# grizzly_bear.net
KiCad netlist of a schematic drawn in EAGLE
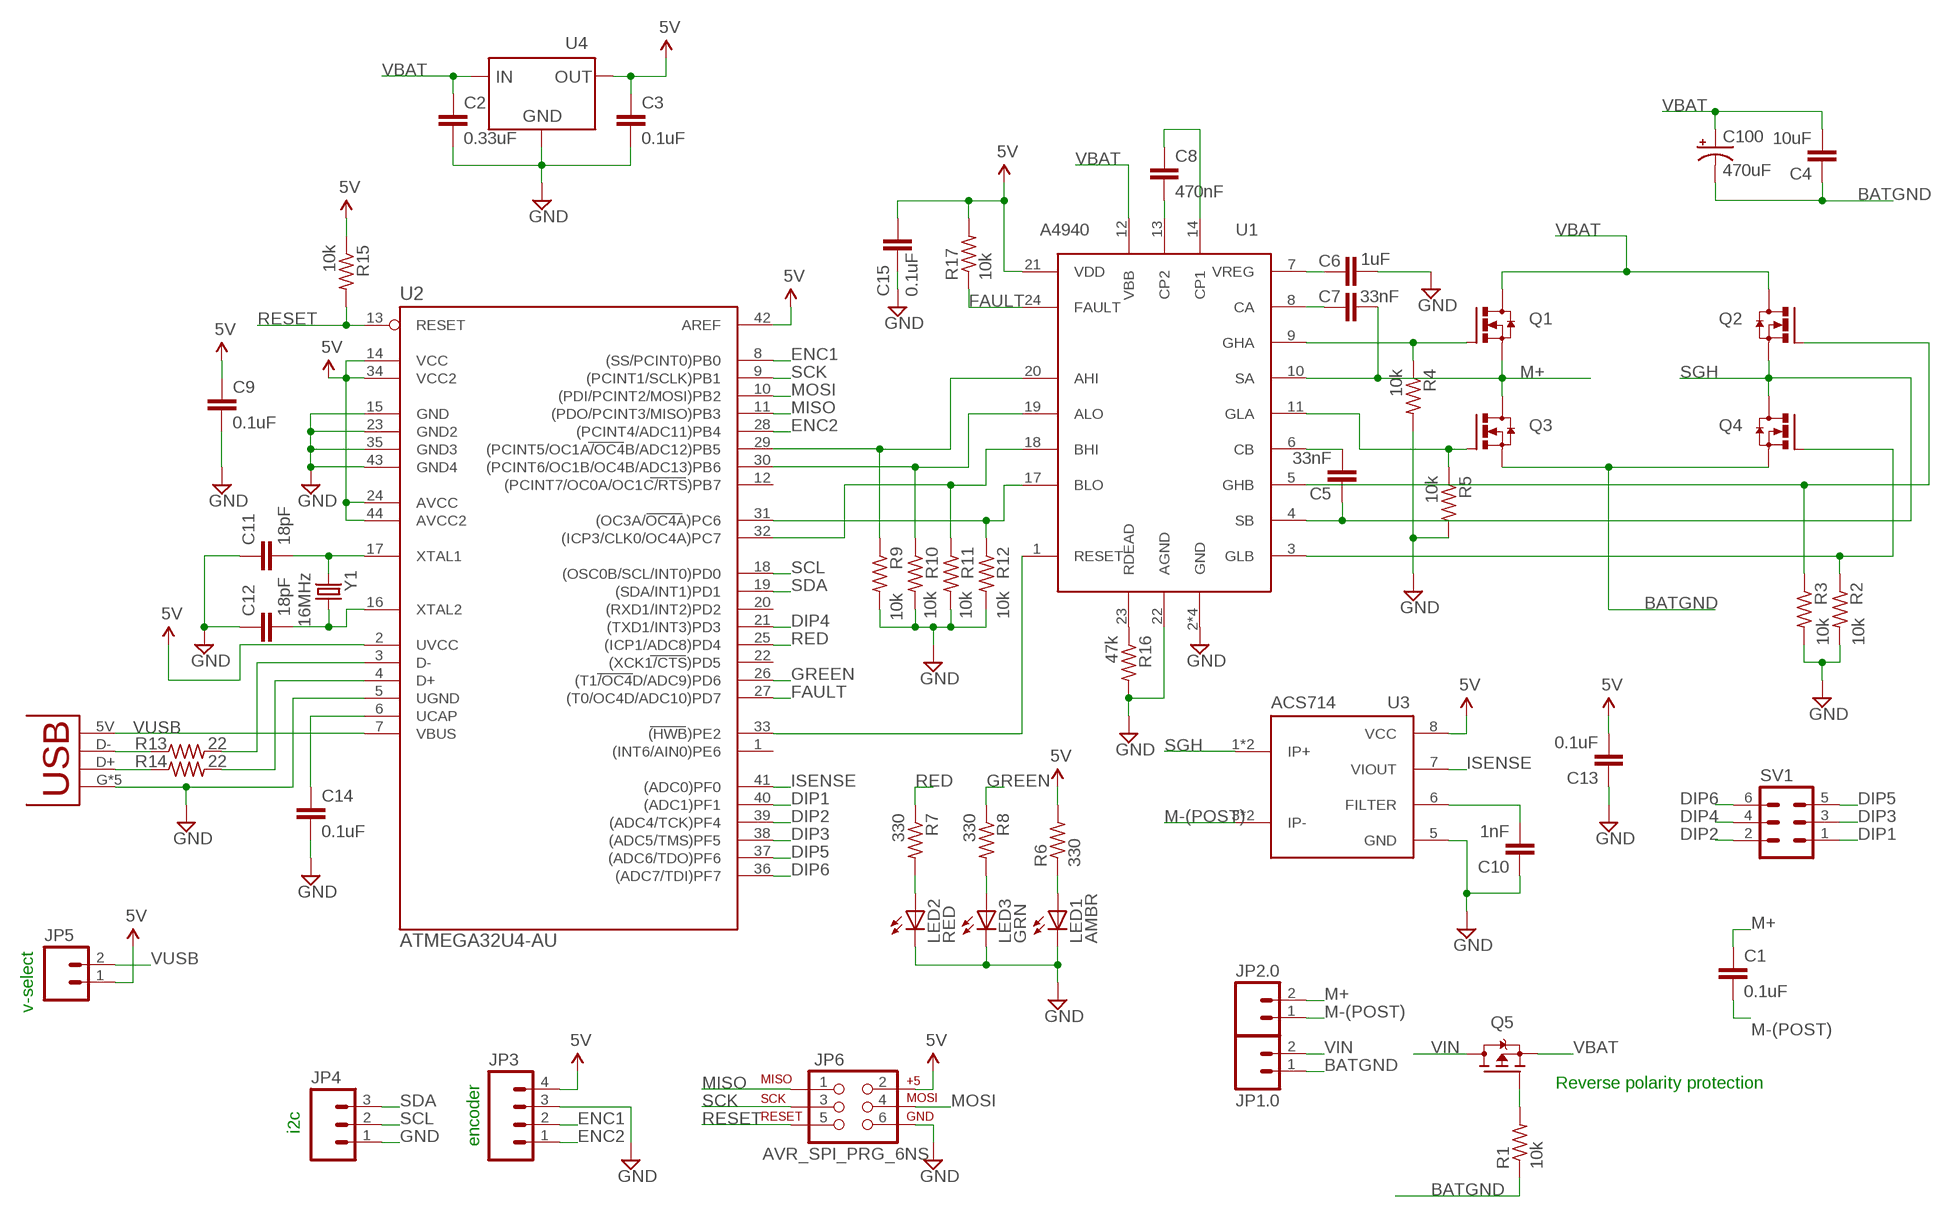
[diagram p0: schematic, sheet 1]

(export (version "E")
  (design (tool "Eeschema 10.0.6"))
  (components
    (comp (ref "C1")
      (value "0.1uF")
      (footprint "eagle-import:0603-CAP")
      (libsource (lib "eagle-import") (part "CAP0603-CAP"))
    )
    (comp (ref "C2")
      (value "0.33uF")
      (footprint "eagle-import:0603-CAP")
      (libsource (lib "eagle-import") (part "CAP0603-CAP"))
    )
    (comp (ref "C3")
      (value "0.1uF")
      (footprint "eagle-import:0603-CAP")
      (libsource (lib "eagle-import") (part "CAP0603-CAP"))
    )
    (comp (ref "C4")
      (value "10uF")
      (footprint "eagle-import:0603-CAP")
      (libsource (lib "eagle-import") (part "CAP0603-CAP"))
    )
    (comp (ref "C5")
      (value "33nF")
      (footprint "eagle-import:0603-CAP")
      (libsource (lib "eagle-import") (part "CAP0603-CAP"))
    )
    (comp (ref "C6")
      (value "1uF")
      (footprint "eagle-import:0603-CAP")
      (libsource (lib "eagle-import") (part "CAP0603-CAP"))
    )
    (comp (ref "C7")
      (value "33nF")
      (footprint "eagle-import:0603-CAP")
      (libsource (lib "eagle-import") (part "CAP0603-CAP"))
    )
    (comp (ref "C8")
      (value "470nF")
      (footprint "eagle-import:0603-CAP")
      (libsource (lib "eagle-import") (part "CAP0603-CAP"))
    )
    (comp (ref "C9")
      (value "0.1uF")
      (footprint "eagle-import:0603-CAP")
      (libsource (lib "eagle-import") (part "CAP0603-CAP"))
    )
    (comp (ref "C10")
      (value "1nF")
      (footprint "eagle-import:0603-CAP")
      (libsource (lib "eagle-import") (part "CAP0603-CAP"))
    )
    (comp (ref "C11")
      (value "18pF")
      (footprint "eagle-import:0603-CAP")
      (libsource (lib "eagle-import") (part "CAP0603-CAP"))
    )
    (comp (ref "C12")
      (value "18pF")
      (footprint "eagle-import:0603-CAP")
      (libsource (lib "eagle-import") (part "CAP0603-CAP"))
    )
    (comp (ref "C13")
      (value "0.1uF")
      (footprint "eagle-import:0603-CAP")
      (libsource (lib "eagle-import") (part "CAP0603-CAP"))
    )
    (comp (ref "C14")
      (value "0.1uF")
      (footprint "eagle-import:0603-CAP")
      (libsource (lib "eagle-import") (part "CAP0603-CAP"))
    )
    (comp (ref "C15")
      (value "0.1uF")
      (footprint "eagle-import:0603-CAP")
      (libsource (lib "eagle-import") (part "CAP0603-CAP"))
    )
    (comp (ref "C100")
      (value "470uF")
      (footprint "eagle-import:PANASONIC_G")
      (libsource (lib "eagle-import") (part "CAP_POLG"))
    )
    (comp (ref "JP1.0")
      (value "M02PTH4")
      (footprint "eagle-import:1X02_XTRA_BIG")
      (libsource (lib "eagle-import") (part "M02PTH4"))
    )
    (comp (ref "JP2.0")
      (value "M02PTH4")
      (footprint "eagle-import:1X02_XTRA_BIG")
      (libsource (lib "eagle-import") (part "M02PTH4"))
    )
    (comp (ref "JP3")
      (value "M04POLAR")
      (footprint "eagle-import:MOLEX-1X4")
      (libsource (lib "eagle-import") (part "M04POLAR"))
    )
    (comp (ref "JP4")
      (value "M03POLAR")
      (footprint "eagle-import:MOLEX-1X3")
      (libsource (lib "eagle-import") (part "M03POLAR"))
    )
    (comp (ref "JP5")
      (value "M02LOCK")
      (footprint "eagle-import:1X02_LOCK")
      (libsource (lib "eagle-import") (part "M02LOCK"))
    )
    (comp (ref "JP6")
      (value "AVR_SPI_PRG_6NS")
      (footprint "eagle-import:2X3-NS")
      (libsource (lib "eagle-import") (part "AVR_SPI_PRG_6NS"))
    )
    (comp (ref "LED1")
      (value "AMBR")
      (footprint "eagle-import:LED-1206")
      (libsource (lib "eagle-import") (part "LED1206"))
    )
    (comp (ref "LED2")
      (value "RED")
      (footprint "eagle-import:LED-1206")
      (libsource (lib "eagle-import") (part "LED1206"))
    )
    (comp (ref "LED3")
      (value "GRN")
      (footprint "eagle-import:LED-1206")
      (libsource (lib "eagle-import") (part "LED1206"))
    )
    (comp (ref "Q1")
      (value "N-CHANNEL-MOSFET")
      (footprint "eagle-import:SOT669")
      (libsource (lib "eagle-import") (part "N-CHANNEL-MOSFET"))
    )
    (comp (ref "Q2")
      (value "N-CHANNEL-MOSFET")
      (footprint "eagle-import:SOT669")
      (libsource (lib "eagle-import") (part "N-CHANNEL-MOSFET"))
    )
    (comp (ref "Q3")
      (value "N-CHANNEL-MOSFET")
      (footprint "eagle-import:SOT669")
      (libsource (lib "eagle-import") (part "N-CHANNEL-MOSFET"))
    )
    (comp (ref "Q4")
      (value "N-CHANNEL-MOSFET")
      (footprint "eagle-import:SOT669")
      (libsource (lib "eagle-import") (part "N-CHANNEL-MOSFET"))
    )
    (comp (ref "Q5")
      (value "IPD90P03P4L")
      (footprint "eagle-import:TO252")
      (libsource (lib "eagle-import") (part "P-CHANNEL-MOSFETTO252"))
    )
    (comp (ref "R1")
      (value "10k")
      (footprint "eagle-import:R0603")
      (libsource (lib "eagle-import") (part "R-US_R0603"))
    )
    (comp (ref "R2")
      (value "10k")
      (footprint "eagle-import:R0603")
      (libsource (lib "eagle-import") (part "R-US_R0603"))
    )
    (comp (ref "R3")
      (value "10k")
      (footprint "eagle-import:R0603")
      (libsource (lib "eagle-import") (part "R-US_R0603"))
    )
    (comp (ref "R4")
      (value "10k")
      (footprint "eagle-import:R0603")
      (libsource (lib "eagle-import") (part "R-US_R0603"))
    )
    (comp (ref "R5")
      (value "10k")
      (footprint "eagle-import:R0603")
      (libsource (lib "eagle-import") (part "R-US_R0603"))
    )
    (comp (ref "R6")
      (value "330")
      (footprint "eagle-import:R0603")
      (libsource (lib "eagle-import") (part "R-US_R0603"))
    )
    (comp (ref "R7")
      (value "330")
      (footprint "eagle-import:R0603")
      (libsource (lib "eagle-import") (part "R-US_R0603"))
    )
    (comp (ref "R8")
      (value "330")
      (footprint "eagle-import:R0603")
      (libsource (lib "eagle-import") (part "R-US_R0603"))
    )
    (comp (ref "R9")
      (value "10k")
      (footprint "eagle-import:R0603")
      (libsource (lib "eagle-import") (part "R-US_R0603"))
    )
    (comp (ref "R10")
      (value "10k")
      (footprint "eagle-import:R0603")
      (libsource (lib "eagle-import") (part "R-US_R0603"))
    )
    (comp (ref "R11")
      (value "10k")
      (footprint "eagle-import:R0603")
      (libsource (lib "eagle-import") (part "R-US_R0603"))
    )
    (comp (ref "R12")
      (value "10k")
      (footprint "eagle-import:R0603")
      (libsource (lib "eagle-import") (part "R-US_R0603"))
    )
    (comp (ref "R13")
      (value "22")
      (footprint "eagle-import:R0603")
      (libsource (lib "eagle-import") (part "R-US_R0603"))
    )
    (comp (ref "R14")
      (value "22")
      (footprint "eagle-import:R0603")
      (libsource (lib "eagle-import") (part "R-US_R0603"))
    )
    (comp (ref "R15")
      (value "10k")
      (footprint "eagle-import:R0603")
      (libsource (lib "eagle-import") (part "R-US_R0603"))
    )
    (comp (ref "R16")
      (value "47k")
      (footprint "eagle-import:R0603")
      (libsource (lib "eagle-import") (part "R-US_R0603"))
    )
    (comp (ref "R17")
      (value "10k")
      (footprint "eagle-import:R0603")
      (libsource (lib "eagle-import") (part "R-US_R0603"))
    )
    (comp (ref "SV1")
      (value "MA03-2")
      (footprint "eagle-import:MA03-2")
      (libsource (lib "eagle-import") (part "MA03-2"))
    )
    (comp (ref "U$2")
      (value "USB-M26FTR")
      (footprint "eagle-import:USB-M26FTR")
      (libsource (lib "eagle-import") (part "USB-M26FTR"))
    )
    (comp (ref "U1")
      (value "A4940")
      (footprint "eagle-import:24-PIN_TSSOP")
      (libsource (lib "eagle-import") (part "A4940"))
    )
    (comp (ref "U2")
      (value "ATMEGA32U4-AU")
      (footprint "eagle-import:TQFP44")
      (libsource (lib "eagle-import") (part "ATMEGA32U4-AU"))
    )
    (comp (ref "U3")
      (value "ACS714")
      (footprint "eagle-import:8-PIN_SOIC")
      (libsource (lib "eagle-import") (part "ACS714"))
    )
    (comp (ref "U4")
      (value "UA78L00")
      (footprint "eagle-import:SOT-89-3")
      (libsource (lib "eagle-import") (part "UA78L00"))
    )
    (comp (ref "Y1")
      (value "16MHz")
      (footprint "eagle-import:HC49US")
      (libsource (lib "eagle-import") (part "CRYSTALHC49US"))
    )
  )
  (nets
    (net (code "1") (name "/BATGND") (class "Default")
      (node (ref "C100") (pin "-") (pinfunction "-_-") (pintype "passive"))
      (node (ref "C4") (pin "1") (pinfunction "1_1") (pintype "passive"))
      (node (ref "JP1.0") (pin "1") (pinfunction "1_1") (pintype "passive"))
      (node (ref "Q3") (pin "1") (pinfunction "S_1") (pintype "passive"))
      (node (ref "Q3") (pin "2") (pinfunction "S_2") (pintype "passive"))
      (node (ref "Q3") (pin "3") (pinfunction "S_3") (pintype "passive"))
      (node (ref "Q4") (pin "1") (pinfunction "S_1") (pintype "passive"))
      (node (ref "Q4") (pin "2") (pinfunction "S_2") (pintype "passive"))
      (node (ref "Q4") (pin "3") (pinfunction "S_3") (pintype "passive"))
      (node (ref "R1") (pin "1") (pinfunction "1_1") (pintype "passive"))
    )
    (net (code "2") (name "/DIP1") (class "Default")
      (node (ref "SV1") (pin "1") (pinfunction "1_1") (pintype "passive"))
      (node (ref "U2") (pin "40") (pinfunction "(ADC1)PF1_40") (pintype "bidirectional"))
    )
    (net (code "3") (name "/DIP2") (class "Default")
      (node (ref "SV1") (pin "2") (pinfunction "2_2") (pintype "passive"))
      (node (ref "U2") (pin "39") (pinfunction "(ADC4/TCK)PF4_39") (pintype "bidirectional"))
    )
    (net (code "4") (name "/DIP3") (class "Default")
      (node (ref "SV1") (pin "3") (pinfunction "3_3") (pintype "passive"))
      (node (ref "U2") (pin "38") (pinfunction "(ADC5/TMS)PF5_38") (pintype "bidirectional"))
    )
    (net (code "5") (name "/DIP4") (class "Default")
      (node (ref "SV1") (pin "4") (pinfunction "4_4") (pintype "passive"))
      (node (ref "U2") (pin "21") (pinfunction "(TXD1/INT3)PD3_21") (pintype "bidirectional"))
    )
    (net (code "6") (name "/DIP5") (class "Default")
      (node (ref "SV1") (pin "5") (pinfunction "5_5") (pintype "passive"))
      (node (ref "U2") (pin "37") (pinfunction "(ADC6/TDO)PF6_37") (pintype "bidirectional"))
    )
    (net (code "7") (name "/DIP6") (class "Default")
      (node (ref "SV1") (pin "6") (pinfunction "6_6") (pintype "passive"))
      (node (ref "U2") (pin "36") (pinfunction "(ADC7/TDI)PF7_36") (pintype "bidirectional"))
    )
    (net (code "8") (name "/ENC1") (class "Default")
      (node (ref "JP3") (pin "2") (pinfunction "2_2") (pintype "passive"))
      (node (ref "U2") (pin "8") (pinfunction "(SS/PCINT0)PB0_8") (pintype "bidirectional"))
    )
    (net (code "9") (name "/ENC2") (class "Default")
      (node (ref "JP3") (pin "1") (pinfunction "1_1") (pintype "passive"))
      (node (ref "U2") (pin "28") (pinfunction "(PCINT4/ADC11)PB4_28") (pintype "bidirectional"))
    )
    (net (code "10") (name "/FAULT") (class "Default")
      (node (ref "R17") (pin "1") (pinfunction "1_1") (pintype "passive"))
      (node (ref "U1") (pin "24") (pinfunction "FAULT_24") (pintype "bidirectional"))
      (node (ref "U2") (pin "27") (pinfunction "(T0/OC4D/ADC10)PD7_27") (pintype "bidirectional"))
    )
    (net (code "11") (name "/GREEN") (class "Default")
      (node (ref "R8") (pin "1") (pinfunction "1_1") (pintype "passive"))
      (node (ref "U2") (pin "26") (pinfunction "(T1/OC4D/ADC9)PD6_26") (pintype "bidirectional"))
    )
    (net (code "12") (name "/ISENSE") (class "Default")
      (node (ref "U2") (pin "41") (pinfunction "(ADC0)PF0_41") (pintype "bidirectional"))
      (node (ref "U3") (pin "7") (pinfunction "VIOUT_7") (pintype "bidirectional"))
    )
    (net (code "13") (name "/M+") (class "Default")
      (node (ref "C1") (pin "1") (pinfunction "1_1") (pintype "passive"))
      (node (ref "C7") (pin "2") (pinfunction "2_2") (pintype "passive"))
      (node (ref "JP2.0") (pin "2") (pinfunction "2_2") (pintype "passive"))
      (node (ref "Q1") (pin "1") (pinfunction "S_1") (pintype "passive"))
      (node (ref "Q1") (pin "2") (pinfunction "S_2") (pintype "passive"))
      (node (ref "Q1") (pin "3") (pinfunction "S_3") (pintype "passive"))
      (node (ref "Q3") (pin "MB") (pinfunction "D_MB") (pintype "passive"))
      (node (ref "U1") (pin "10") (pinfunction "SA_10") (pintype "bidirectional"))
    )
    (net (code "14") (name "/M-(POST)") (class "Default")
      (node (ref "C1") (pin "2") (pinfunction "2_2") (pintype "passive"))
      (node (ref "JP2.0") (pin "1") (pinfunction "1_1") (pintype "passive"))
      (node (ref "U3") (pin "3") (pinfunction "IP-_3") (pintype "bidirectional"))
      (node (ref "U3") (pin "4") (pinfunction "IP-_4") (pintype "bidirectional"))
    )
    (net (code "15") (name "/MISO") (class "Default")
      (node (ref "JP6") (pin "1") (pinfunction "1_1") (pintype "passive"))
      (node (ref "U2") (pin "11") (pinfunction "(PDO/PCINT3/MISO)PB3_11") (pintype "bidirectional"))
    )
    (net (code "16") (name "/MOSI") (class "Default")
      (node (ref "JP6") (pin "4") (pinfunction "4_4") (pintype "passive"))
      (node (ref "U2") (pin "10") (pinfunction "(PDI/PCINT2/MOSI)PB2_10") (pintype "bidirectional"))
    )
    (net (code "17") (name "/RED") (class "Default")
      (node (ref "R7") (pin "1") (pinfunction "1_1") (pintype "passive"))
      (node (ref "U2") (pin "25") (pinfunction "(ICP1/ADC8)PD4_25") (pintype "bidirectional"))
    )
    (net (code "18") (name "/RESET") (class "Default")
      (node (ref "JP6") (pin "5") (pinfunction "5_5") (pintype "passive"))
      (node (ref "R15") (pin "2") (pinfunction "2_2") (pintype "passive"))
      (node (ref "U2") (pin "13") (pinfunction "RESET_13") (pintype "bidirectional"))
    )
    (net (code "19") (name "/SCK") (class "Default")
      (node (ref "JP6") (pin "3") (pinfunction "3_3") (pintype "passive"))
      (node (ref "U2") (pin "9") (pinfunction "(PCINT1/SCLK)PB1_9") (pintype "bidirectional"))
    )
    (net (code "20") (name "/SCL") (class "Default")
      (node (ref "JP4") (pin "2") (pinfunction "2_2") (pintype "passive"))
      (node (ref "U2") (pin "18") (pinfunction "(OSC0B/SCL/INT0)PD0_18") (pintype "bidirectional"))
    )
    (net (code "21") (name "/SDA") (class "Default")
      (node (ref "JP4") (pin "3") (pinfunction "3_3") (pintype "passive"))
      (node (ref "U2") (pin "19") (pinfunction "(SDA/INT1)PD1_19") (pintype "bidirectional"))
    )
    (net (code "22") (name "/SGH") (class "Default")
      (node (ref "C5") (pin "1") (pinfunction "1_1") (pintype "passive"))
      (node (ref "Q2") (pin "1") (pinfunction "S_1") (pintype "passive"))
      (node (ref "Q2") (pin "2") (pinfunction "S_2") (pintype "passive"))
      (node (ref "Q2") (pin "3") (pinfunction "S_3") (pintype "passive"))
      (node (ref "Q4") (pin "MB") (pinfunction "D_MB") (pintype "passive"))
      (node (ref "U1") (pin "4") (pinfunction "SB_4") (pintype "bidirectional"))
      (node (ref "U3") (pin "1") (pinfunction "IP+_1") (pintype "bidirectional"))
      (node (ref "U3") (pin "2") (pinfunction "IP+_2") (pintype "bidirectional"))
    )
    (net (code "23") (name "/VBAT") (class "Default")
      (node (ref "C100") (pin "+") (pinfunction "+_+") (pintype "passive"))
      (node (ref "C2") (pin "1") (pinfunction "1_1") (pintype "passive"))
      (node (ref "C4") (pin "2") (pinfunction "2_2") (pintype "passive"))
      (node (ref "Q1") (pin "MB") (pinfunction "D_MB") (pintype "passive"))
      (node (ref "Q2") (pin "MB") (pinfunction "D_MB") (pintype "passive"))
      (node (ref "Q5") (pin "2") (pinfunction "S_2") (pintype "passive"))
      (node (ref "U1") (pin "12") (pinfunction "VBB_12") (pintype "bidirectional"))
      (node (ref "U4") (pin "INPUT") (pinfunction "IN_INPUT") (pintype "bidirectional"))
    )
    (net (code "24") (name "/VIN") (class "Default")
      (node (ref "JP1.0") (pin "2") (pinfunction "2_2") (pintype "passive"))
      (node (ref "Q5") (pin "3") (pinfunction "D_3") (pintype "passive"))
    )
    (net (code "25") (name "/VUSB") (class "Default")
      (node (ref "JP5") (pin "2") (pinfunction "2_2") (pintype "passive"))
      (node (ref "U$2") (pin "5V") (pinfunction "5V_5V") (pintype "bidirectional"))
      (node (ref "U2") (pin "7") (pinfunction "VBUS_7") (pintype "bidirectional"))
    )
    (net (code "26") (name "5V") (class "Default")
      (node (ref "C13") (pin "2") (pinfunction "2_2") (pintype "passive"))
      (node (ref "C15") (pin "1") (pinfunction "1_1") (pintype "passive"))
      (node (ref "C3") (pin "1") (pinfunction "1_1") (pintype "passive"))
      (node (ref "C9") (pin "1") (pinfunction "1_1") (pintype "passive"))
      (node (ref "JP3") (pin "4") (pinfunction "4_4") (pintype "passive"))
      (node (ref "JP5") (pin "1") (pinfunction "1_1") (pintype "passive"))
      (node (ref "JP6") (pin "2") (pinfunction "2_2") (pintype "passive"))
      (node (ref "R15") (pin "1") (pinfunction "1_1") (pintype "passive"))
      (node (ref "R17") (pin "2") (pinfunction "2_2") (pintype "passive"))
      (node (ref "R6") (pin "2") (pinfunction "2_2") (pintype "passive"))
      (node (ref "U1") (pin "21") (pinfunction "VDD_21") (pintype "bidirectional"))
      (node (ref "U2") (pin "14") (pinfunction "VCC_14") (pintype "bidirectional"))
      (node (ref "U2") (pin "2") (pinfunction "UVCC_2") (pintype "bidirectional"))
      (node (ref "U2") (pin "24") (pinfunction "AVCC_24") (pintype "bidirectional"))
      (node (ref "U2") (pin "34") (pinfunction "VCC2_34") (pintype "bidirectional"))
      (node (ref "U2") (pin "42") (pinfunction "AREF_42") (pintype "bidirectional"))
      (node (ref "U2") (pin "44") (pinfunction "AVCC2_44") (pintype "bidirectional"))
      (node (ref "U3") (pin "8") (pinfunction "VCC_8") (pintype "bidirectional"))
      (node (ref "U4") (pin "OUTPUT") (pinfunction "OUT_OUTPUT") (pintype "bidirectional"))
    )
    (net (code "27") (name "GND") (class "Default")
      (node (ref "C10") (pin "1") (pinfunction "1_1") (pintype "passive"))
      (node (ref "C11") (pin "1") (pinfunction "1_1") (pintype "passive"))
      (node (ref "C12") (pin "1") (pinfunction "1_1") (pintype "passive"))
      (node (ref "C13") (pin "1") (pinfunction "1_1") (pintype "passive"))
      (node (ref "C14") (pin "2") (pinfunction "2_2") (pintype "passive"))
      (node (ref "C15") (pin "2") (pinfunction "2_2") (pintype "passive"))
      (node (ref "C2") (pin "2") (pinfunction "2_2") (pintype "passive"))
      (node (ref "C3") (pin "2") (pinfunction "2_2") (pintype "passive"))
      (node (ref "C6") (pin "2") (pinfunction "2_2") (pintype "passive"))
      (node (ref "C9") (pin "2") (pinfunction "2_2") (pintype "passive"))
      (node (ref "JP3") (pin "3") (pinfunction "3_3") (pintype "passive"))
      (node (ref "JP4") (pin "1") (pinfunction "1_1") (pintype "passive"))
      (node (ref "JP6") (pin "6") (pinfunction "6_6") (pintype "passive"))
      (node (ref "LED1") (pin "C") (pinfunction "C_C") (pintype "passive"))
      (node (ref "LED2") (pin "C") (pinfunction "C_C") (pintype "passive"))
      (node (ref "LED3") (pin "C") (pinfunction "C_C") (pintype "passive"))
      (node (ref "R10") (pin "2") (pinfunction "2_2") (pintype "passive"))
      (node (ref "R11") (pin "2") (pinfunction "2_2") (pintype "passive"))
      (node (ref "R12") (pin "2") (pinfunction "2_2") (pintype "passive"))
      (node (ref "R16") (pin "2") (pinfunction "2_2") (pintype "passive"))
      (node (ref "R2") (pin "2") (pinfunction "2_2") (pintype "passive"))
      (node (ref "R3") (pin "2") (pinfunction "2_2") (pintype "passive"))
      (node (ref "R4") (pin "2") (pinfunction "2_2") (pintype "passive"))
      (node (ref "R5") (pin "2") (pinfunction "2_2") (pintype "passive"))
      (node (ref "R9") (pin "2") (pinfunction "2_2") (pintype "passive"))
      (node (ref "U$2") (pin "G") (pinfunction "G_G") (pintype "bidirectional"))
      (node (ref "U$2") (pin "S1") (pinfunction "G_S1") (pintype "bidirectional"))
      (node (ref "U$2") (pin "S2") (pinfunction "G_S2") (pintype "bidirectional"))
      (node (ref "U$2") (pin "S3") (pinfunction "G_S3") (pintype "bidirectional"))
      (node (ref "U$2") (pin "S4") (pinfunction "G_S4") (pintype "bidirectional"))
      (node (ref "U1") (pin "15") (pinfunction "GND_15") (pintype "bidirectional"))
      (node (ref "U1") (pin "16") (pinfunction "GND_16") (pintype "bidirectional"))
      (node (ref "U1") (pin "2") (pinfunction "GND_2") (pintype "bidirectional"))
      (node (ref "U1") (pin "22") (pinfunction "AGND_22") (pintype "bidirectional"))
      (node (ref "U1") (pin "PAD") (pinfunction "GND_PAD") (pintype "bidirectional"))
      (node (ref "U2") (pin "15") (pinfunction "GND_15") (pintype "bidirectional"))
      (node (ref "U2") (pin "23") (pinfunction "GND2_23") (pintype "bidirectional"))
      (node (ref "U2") (pin "35") (pinfunction "GND3_35") (pintype "bidirectional"))
      (node (ref "U2") (pin "43") (pinfunction "GND4_43") (pintype "bidirectional"))
      (node (ref "U2") (pin "5") (pinfunction "UGND_5") (pintype "bidirectional"))
      (node (ref "U3") (pin "5") (pinfunction "GND_5") (pintype "bidirectional"))
      (node (ref "U4") (pin "COMMON") (pinfunction "GND_COMMON") (pintype "bidirectional"))
    )
    (net (code "28") (name "Net-(LED1-PadA)") (class "Default")
      (node (ref "LED1") (pin "A") (pinfunction "A_A") (pintype "passive"))
      (node (ref "R6") (pin "1") (pinfunction "1_1") (pintype "passive"))
    )
    (net (code "29") (name "Net-(LED2-PadA)") (class "Default")
      (node (ref "LED2") (pin "A") (pinfunction "A_A") (pintype "passive"))
      (node (ref "R7") (pin "2") (pinfunction "2_2") (pintype "passive"))
    )
    (net (code "30") (name "Net-(LED3-PadA)") (class "Default")
      (node (ref "LED3") (pin "A") (pinfunction "A_A") (pintype "passive"))
      (node (ref "R8") (pin "2") (pinfunction "2_2") (pintype "passive"))
    )
    (net (code "31") (name "Net-(Q1-G)") (class "Default")
      (node (ref "Q1") (pin "4") (pinfunction "G_4") (pintype "passive"))
      (node (ref "R4") (pin "1") (pinfunction "1_1") (pintype "passive"))
      (node (ref "U1") (pin "9") (pinfunction "GHA_9") (pintype "bidirectional"))
    )
    (net (code "32") (name "Net-(Q2-G)") (class "Default")
      (node (ref "Q2") (pin "4") (pinfunction "G_4") (pintype "passive"))
      (node (ref "R3") (pin "1") (pinfunction "1_1") (pintype "passive"))
      (node (ref "U1") (pin "5") (pinfunction "GHB_5") (pintype "bidirectional"))
    )
    (net (code "33") (name "Net-(Q3-G)") (class "Default")
      (node (ref "Q3") (pin "4") (pinfunction "G_4") (pintype "passive"))
      (node (ref "R5") (pin "1") (pinfunction "1_1") (pintype "passive"))
      (node (ref "U1") (pin "11") (pinfunction "GLA_11") (pintype "bidirectional"))
    )
    (net (code "34") (name "Net-(Q4-G)") (class "Default")
      (node (ref "Q4") (pin "4") (pinfunction "G_4") (pintype "passive"))
      (node (ref "R2") (pin "1") (pinfunction "1_1") (pintype "passive"))
      (node (ref "U1") (pin "3") (pinfunction "GLB_3") (pintype "bidirectional"))
    )
    (net (code "35") (name "Net-(Q5-G)") (class "Default")
      (node (ref "Q5") (pin "1") (pinfunction "G_1") (pintype "passive"))
      (node (ref "R1") (pin "2") (pinfunction "2_2") (pintype "passive"))
    )
    (net (code "36") (name "Net-(R13-Pad1)") (class "Default")
      (node (ref "R13") (pin "1") (pinfunction "1_1") (pintype "passive"))
      (node (ref "U$2") (pin "D-") (pinfunction "D-_D-") (pintype "bidirectional"))
    )
    (net (code "37") (name "Net-(R14-Pad1)") (class "Default")
      (node (ref "R14") (pin "1") (pinfunction "1_1") (pintype "passive"))
      (node (ref "U$2") (pin "D+") (pinfunction "D+_D+") (pintype "bidirectional"))
    )
    (net (code "38") (name "Net-(U1-AHI)") (class "Default")
      (node (ref "R9") (pin "1") (pinfunction "1_1") (pintype "passive"))
      (node (ref "U1") (pin "20") (pinfunction "AHI_20") (pintype "bidirectional"))
      (node (ref "U2") (pin "29") (pinfunction "(PCINT5/OC1A/OC4B/ADC12)PB5_29") (pintype "bidirectional"))
    )
    (net (code "39") (name "Net-(U1-ALO)") (class "Default")
      (node (ref "R10") (pin "1") (pinfunction "1_1") (pintype "passive"))
      (node (ref "U1") (pin "19") (pinfunction "ALO_19") (pintype "bidirectional"))
      (node (ref "U2") (pin "30") (pinfunction "(PCINT6/OC1B/OC4B/ADC13)PB6_30") (pintype "bidirectional"))
    )
    (net (code "40") (name "Net-(U1-BHI)") (class "Default")
      (node (ref "R11") (pin "1") (pinfunction "1_1") (pintype "passive"))
      (node (ref "U1") (pin "18") (pinfunction "BHI_18") (pintype "bidirectional"))
      (node (ref "U2") (pin "32") (pinfunction "(ICP3/CLK0/OC4A)PC7_32") (pintype "bidirectional"))
    )
    (net (code "41") (name "Net-(U1-BLO)") (class "Default")
      (node (ref "R12") (pin "1") (pinfunction "1_1") (pintype "passive"))
      (node (ref "U1") (pin "17") (pinfunction "BLO_17") (pintype "bidirectional"))
      (node (ref "U2") (pin "31") (pinfunction "(OC3A/OC4A)PC6_31") (pintype "bidirectional"))
    )
    (net (code "42") (name "Net-(U1-CA)") (class "Default")
      (node (ref "C7") (pin "1") (pinfunction "1_1") (pintype "passive"))
      (node (ref "U1") (pin "8") (pinfunction "CA_8") (pintype "bidirectional"))
    )
    (net (code "43") (name "Net-(U1-CB)") (class "Default")
      (node (ref "C5") (pin "2") (pinfunction "2_2") (pintype "passive"))
      (node (ref "U1") (pin "6") (pinfunction "CB_6") (pintype "bidirectional"))
    )
    (net (code "44") (name "Net-(U1-CP1)") (class "Default")
      (node (ref "C8") (pin "1") (pinfunction "1_1") (pintype "passive"))
      (node (ref "U1") (pin "14") (pinfunction "CP1_14") (pintype "bidirectional"))
    )
    (net (code "45") (name "Net-(U1-CP2)") (class "Default")
      (node (ref "C8") (pin "2") (pinfunction "2_2") (pintype "passive"))
      (node (ref "U1") (pin "13") (pinfunction "CP2_13") (pintype "bidirectional"))
    )
    (net (code "46") (name "Net-(U1-RDEAD)") (class "Default")
      (node (ref "R16") (pin "1") (pinfunction "1_1") (pintype "passive"))
      (node (ref "U1") (pin "23") (pinfunction "RDEAD_23") (pintype "bidirectional"))
    )
    (net (code "47") (name "Net-(U1-RESET)") (class "Default")
      (node (ref "U1") (pin "1") (pinfunction "RESET_1") (pintype "bidirectional"))
      (node (ref "U2") (pin "33") (pinfunction "(HWB)PE2_33") (pintype "bidirectional"))
    )
    (net (code "48") (name "Net-(U1-VREG)") (class "Default")
      (node (ref "C6") (pin "1") (pinfunction "1_1") (pintype "passive"))
      (node (ref "U1") (pin "7") (pinfunction "VREG_7") (pintype "bidirectional"))
    )
    (net (code "49") (name "Net-(U2-D+)") (class "Default")
      (node (ref "R14") (pin "2") (pinfunction "2_2") (pintype "passive"))
      (node (ref "U2") (pin "4") (pinfunction "D+_4") (pintype "bidirectional"))
    )
    (net (code "50") (name "Net-(U2-D-)") (class "Default")
      (node (ref "R13") (pin "2") (pinfunction "2_2") (pintype "passive"))
      (node (ref "U2") (pin "3") (pinfunction "D-_3") (pintype "bidirectional"))
    )
    (net (code "51") (name "Net-(U2-UCAP)") (class "Default")
      (node (ref "C14") (pin "1") (pinfunction "1_1") (pintype "passive"))
      (node (ref "U2") (pin "6") (pinfunction "UCAP_6") (pintype "bidirectional"))
    )
    (net (code "52") (name "Net-(U2-XTAL1)") (class "Default")
      (node (ref "C11") (pin "2") (pinfunction "2_2") (pintype "passive"))
      (node (ref "U2") (pin "17") (pinfunction "XTAL1_17") (pintype "bidirectional"))
      (node (ref "Y1") (pin "2") (pinfunction "2_2") (pintype "passive"))
    )
    (net (code "53") (name "Net-(U2-XTAL2)") (class "Default")
      (node (ref "C12") (pin "2") (pinfunction "2_2") (pintype "passive"))
      (node (ref "U2") (pin "16") (pinfunction "XTAL2_16") (pintype "bidirectional"))
      (node (ref "Y1") (pin "1") (pinfunction "1_1") (pintype "passive"))
    )
    (net (code "54") (name "Net-(U3-FILTER)") (class "Default")
      (node (ref "C10") (pin "2") (pinfunction "2_2") (pintype "passive"))
      (node (ref "U3") (pin "6") (pinfunction "FILTER_6") (pintype "bidirectional"))
    )
    (net (code "55") (name "unconnected-(U2-(INT6{slash}AIN0)PE6-Pad1)") (class "Default")
      (node (ref "U2") (pin "1") (pinfunction "(INT6/AIN0)PE6_1") (pintype "bidirectional"))
    )
    (net (code "56") (name "unconnected-(U2-(PCINT7{slash}OC0A{slash}OC1C{slash}RTS)PB7-Pad12)") (class "Default")
      (node (ref "U2") (pin "12") (pinfunction "(PCINT7/OC0A/OC1C/RTS)PB7_12") (pintype "bidirectional"))
    )
    (net (code "57") (name "unconnected-(U2-(RXD1{slash}INT2)PD2-Pad20)") (class "Default")
      (node (ref "U2") (pin "20") (pinfunction "(RXD1/INT2)PD2_20") (pintype "bidirectional"))
    )
    (net (code "58") (name "unconnected-(U2-(XCK1{slash}CTS)PD5-Pad22)") (class "Default")
      (node (ref "U2") (pin "22") (pinfunction "(XCK1/CTS)PD5_22") (pintype "bidirectional"))
    )
  )
)
